# ir2104_V2_0.net
KiCad netlist of a schematic drawn in EasyEDA Pro
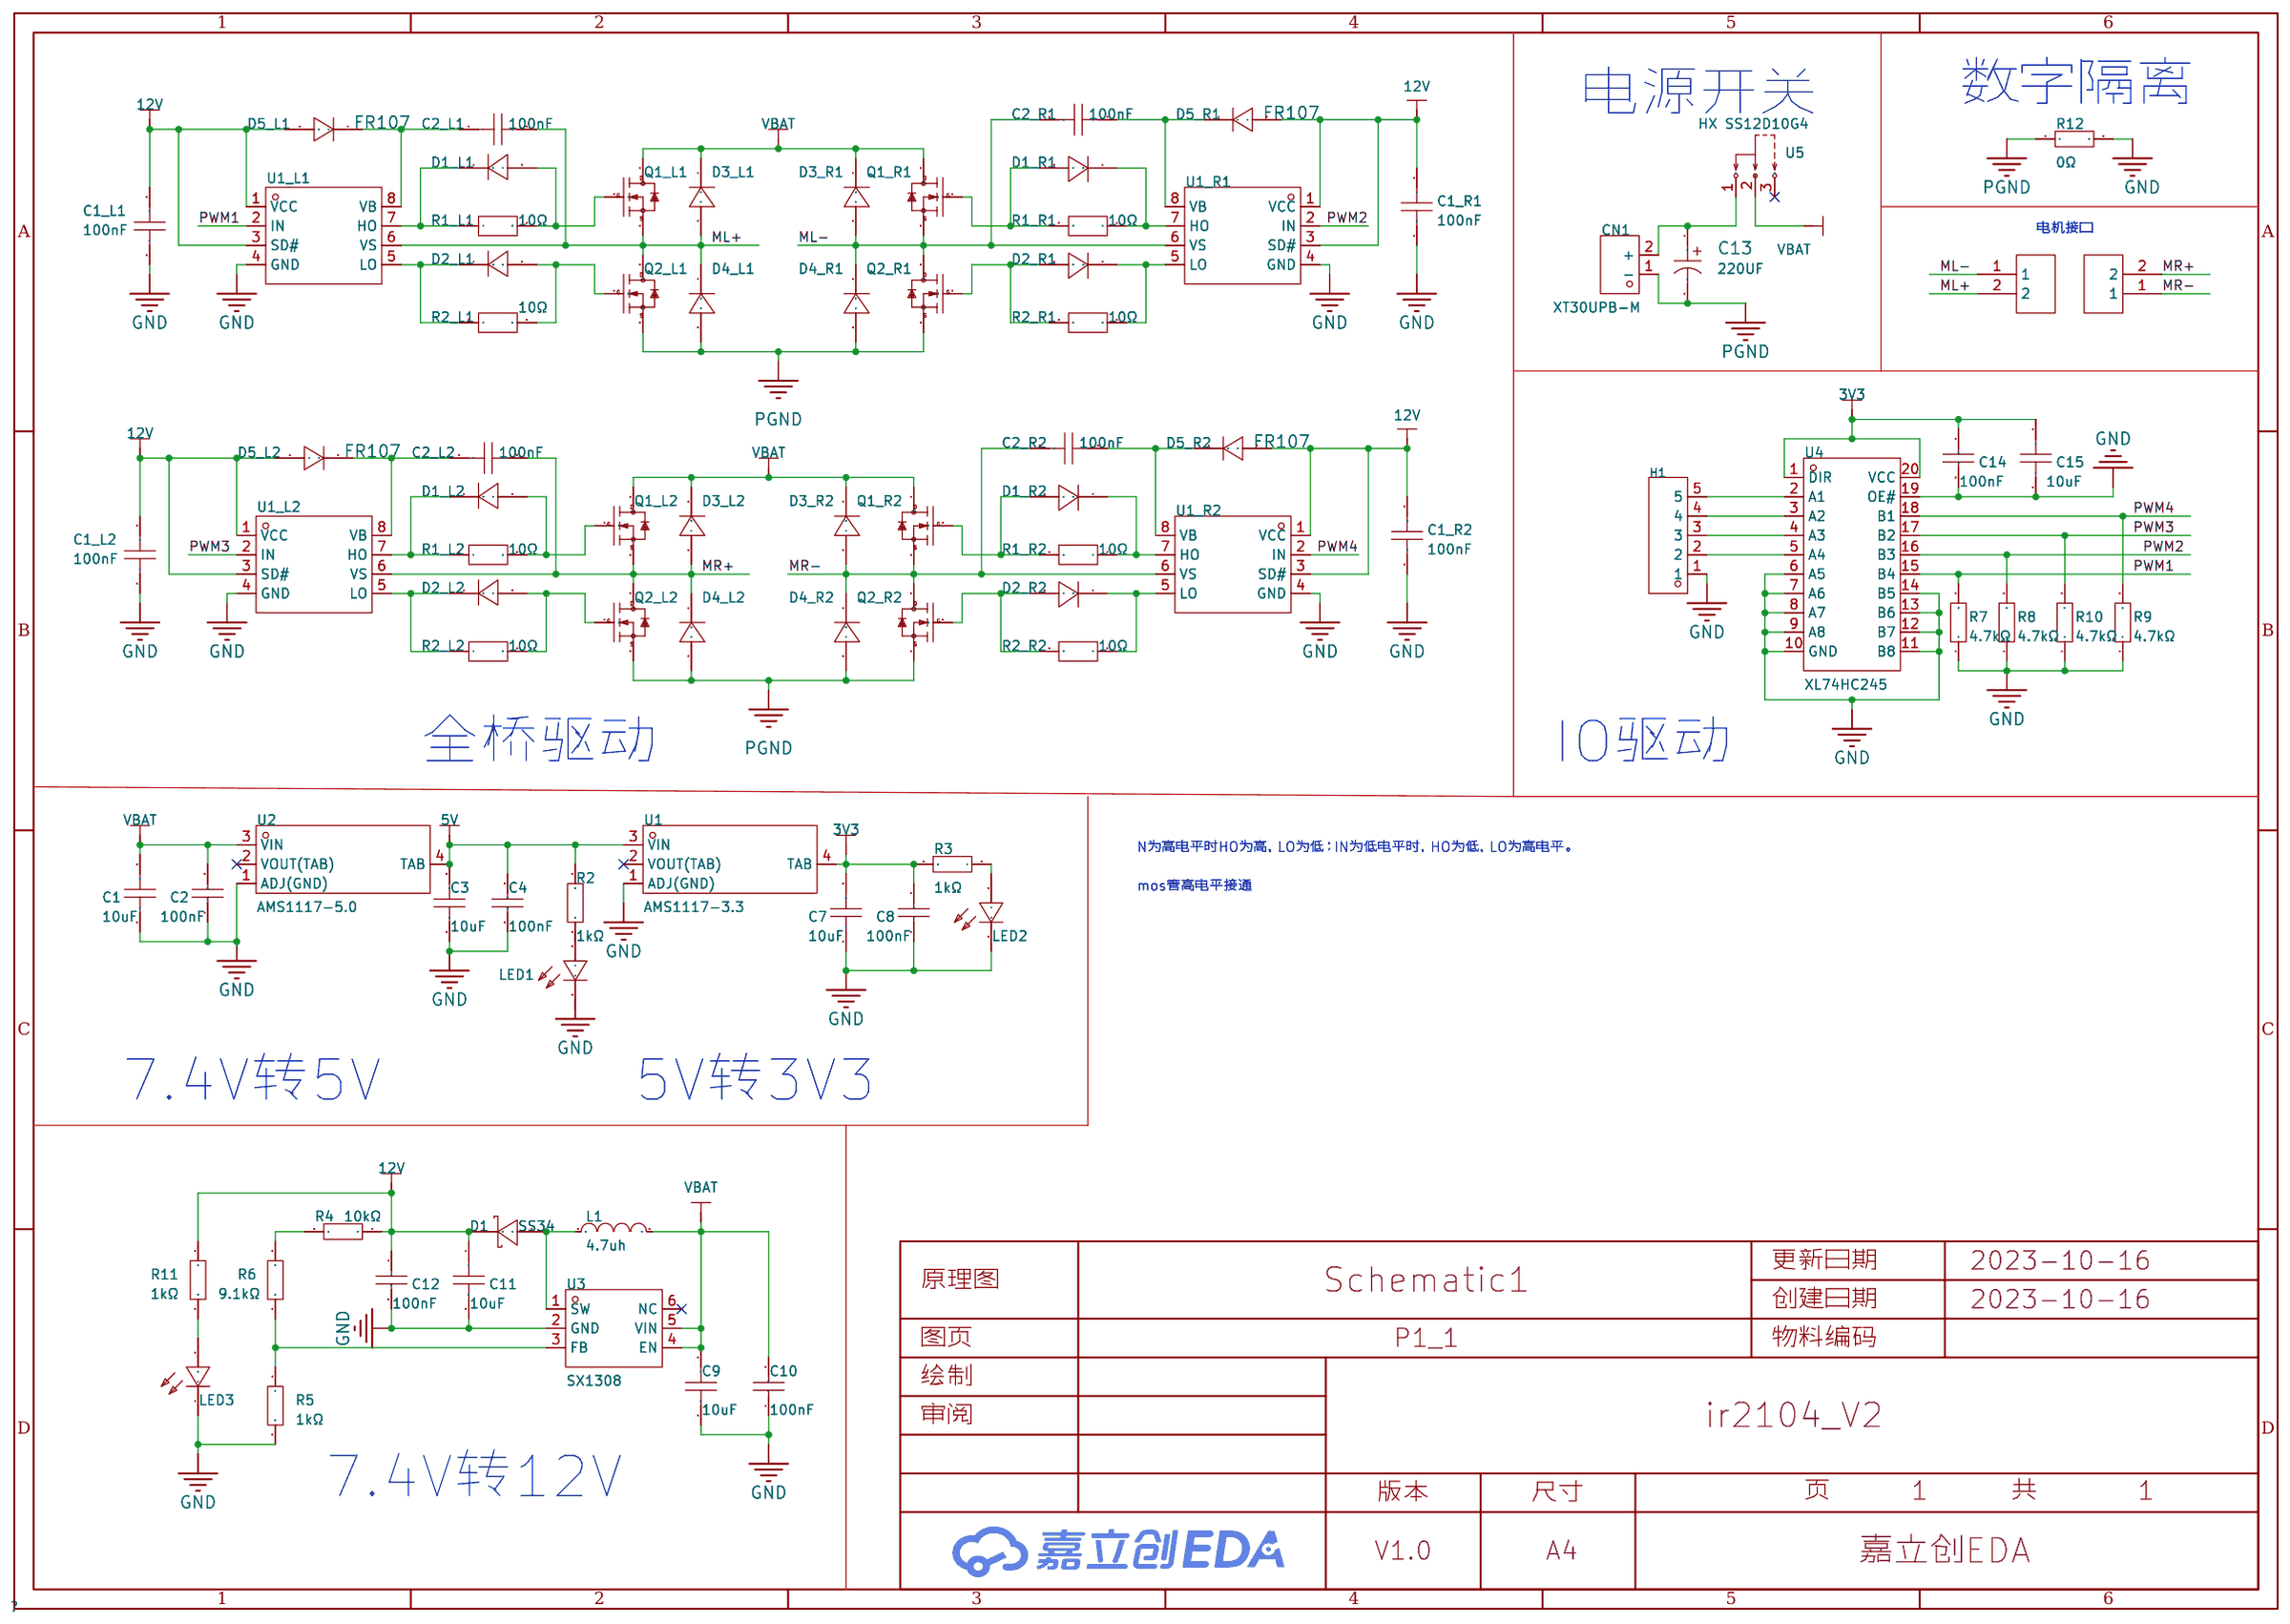
[diagram p0: schematic sheet]

(export (version "E")
  (design (tool "Eeschema 10.0.6"))
  (components
    (comp (ref "C1")
      (value "10uF")
      (footprint "easyedapro:C0603")
      (description "容值:10uF;精度:±20%;额定电压:25V;材质(温度系数):X5R;")
      (fields
        (field (name "Manufacturer Part") "CL10A106MA8NRNC")
        (field (name "Manufacturer") "SAMSUNG(三星)")
      )
      (libsource (lib "easyedapro") (part "CL10A106MA8NRNC"))
    )
    (comp (ref "C1_L1")
      (value "100nF")
      (footprint "easyedapro:C0603")
      (description "容值:100nF;精度:±10%;额定电压:50V;材质(温度系数):X7R;")
      (fields
        (field (name "Manufacturer Part") "CL10B104KB8NNNC")
        (field (name "Manufacturer") "SAMSUNG(三星)")
      )
      (libsource (lib "easyedapro") (part "CL10B104KB8NNNC"))
    )
    (comp (ref "C1_L2")
      (value "100nF")
      (footprint "easyedapro:C0603")
      (description "容值:100nF;精度:±10%;额定电压:50V;材质(温度系数):X7R;")
      (fields
        (field (name "Manufacturer Part") "CL10B104KB8NNNC")
        (field (name "Manufacturer") "SAMSUNG(三星)")
      )
      (libsource (lib "easyedapro") (part "CL10B104KB8NNNC"))
    )
    (comp (ref "C1_R1")
      (value "100nF")
      (footprint "easyedapro:C0603")
      (description "容值:100nF;精度:±10%;额定电压:50V;材质(温度系数):X7R;")
      (fields
        (field (name "Manufacturer Part") "CL10B104KB8NNNC")
        (field (name "Manufacturer") "SAMSUNG(三星)")
      )
      (libsource (lib "easyedapro") (part "CL10B104KB8NNNC"))
    )
    (comp (ref "C1_R2")
      (value "100nF")
      (footprint "easyedapro:C0603")
      (description "容值:100nF;精度:±10%;额定电压:50V;材质(温度系数):X7R;")
      (fields
        (field (name "Manufacturer Part") "CL10B104KB8NNNC")
        (field (name "Manufacturer") "SAMSUNG(三星)")
      )
      (libsource (lib "easyedapro") (part "CL10B104KB8NNNC"))
    )
    (comp (ref "C2")
      (value "100nF")
      (footprint "easyedapro:C0603")
      (description "容值:100nF;精度:±10%;额定电压:50V;材质(温度系数):X7R;")
      (fields (field (name "Manufacturer Part") "0603B104K500NT") (field (name "Manufacturer") "FH(风华)"))
      (libsource (lib "easyedapro") (part "0603B104K500NT"))
    )
    (comp (ref "C2_L1")
      (value "100nF")
      (footprint "easyedapro:C0603")
      (description "容值:100nF;精度:±10%;额定电压:50V;材质(温度系数):X7R;")
      (fields
        (field (name "Manufacturer Part") "CL10B104KB8NNNC")
        (field (name "Manufacturer") "SAMSUNG(三星)")
      )
      (libsource (lib "easyedapro") (part "CL10B104KB8NNNC"))
    )
    (comp (ref "C2_L2")
      (value "100nF")
      (footprint "easyedapro:C0603")
      (description "容值:100nF;精度:±10%;额定电压:50V;材质(温度系数):X7R;")
      (fields
        (field (name "Manufacturer Part") "CL10B104KB8NNNC")
        (field (name "Manufacturer") "SAMSUNG(三星)")
      )
      (libsource (lib "easyedapro") (part "CL10B104KB8NNNC"))
    )
    (comp (ref "C2_R1")
      (value "100nF")
      (footprint "easyedapro:C0603")
      (description "容值:100nF;精度:±10%;额定电压:50V;材质(温度系数):X7R;")
      (fields
        (field (name "Manufacturer Part") "CL10B104KB8NNNC")
        (field (name "Manufacturer") "SAMSUNG(三星)")
      )
      (libsource (lib "easyedapro") (part "CL10B104KB8NNNC"))
    )
    (comp (ref "C2_R2")
      (value "100nF")
      (footprint "easyedapro:C0603")
      (description "容值:100nF;精度:±10%;额定电压:50V;材质(温度系数):X7R;")
      (fields
        (field (name "Manufacturer Part") "CL10B104KB8NNNC")
        (field (name "Manufacturer") "SAMSUNG(三星)")
      )
      (libsource (lib "easyedapro") (part "CL10B104KB8NNNC"))
    )
    (comp (ref "C3")
      (value "10uF")
      (footprint "easyedapro:C0603")
      (description "容值:10uF;精度:±20%;额定电压:25V;材质(温度系数):X5R;")
      (fields
        (field (name "Manufacturer Part") "CL10A106MA8NRNC")
        (field (name "Manufacturer") "SAMSUNG(三星)")
      )
      (libsource (lib "easyedapro") (part "CL10A106MA8NRNC"))
    )
    (comp (ref "C4")
      (value "100nF")
      (footprint "easyedapro:C0603")
      (description "容值:100nF;精度:±10%;额定电压:50V;材质(温度系数):X7R;")
      (fields (field (name "Manufacturer Part") "0603B104K500NT") (field (name "Manufacturer") "FH(风华)"))
      (libsource (lib "easyedapro") (part "0603B104K500NT"))
    )
    (comp (ref "C7")
      (value "10uF")
      (footprint "easyedapro:C0603")
      (description "容值:10uF;精度:±20%;额定电压:25V;材质(温度系数):X5R;")
      (fields
        (field (name "Manufacturer Part") "CL10A106MA8NRNC")
        (field (name "Manufacturer") "SAMSUNG(三星)")
      )
      (libsource (lib "easyedapro") (part "CL10A106MA8NRNC"))
    )
    (comp (ref "C8")
      (value "100nF")
      (footprint "easyedapro:C0603")
      (description "容值:100nF;精度:±10%;额定电压:50V;材质(温度系数):X7R;")
      (fields (field (name "Manufacturer Part") "0603B104K500NT") (field (name "Manufacturer") "FH(风华)"))
      (libsource (lib "easyedapro") (part "0603B104K500NT"))
    )
    (comp (ref "C9")
      (value "10uF")
      (footprint "easyedapro:C0603")
      (description "容值:10uF;精度:±20%;额定电压:25V;材质(温度系数):X5R;")
      (fields
        (field (name "Manufacturer Part") "CL10A106MA8NRNC")
        (field (name "Manufacturer") "SAMSUNG(三星)")
      )
      (libsource (lib "easyedapro") (part "CL10A106MA8NRNC"))
    )
    (comp (ref "C10")
      (value "100nF")
      (footprint "easyedapro:C0603")
      (description "容值:100nF;精度:±10%;额定电压:50V;材质(温度系数):X7R;")
      (fields (field (name "Manufacturer Part") "0603B104K500NT") (field (name "Manufacturer") "FH(风华)"))
      (libsource (lib "easyedapro") (part "0603B104K500NT"))
    )
    (comp (ref "C11")
      (value "10uF")
      (footprint "easyedapro:C0603")
      (description "容值:10uF;精度:±20%;额定电压:25V;材质(温度系数):X5R;")
      (fields
        (field (name "Manufacturer Part") "CL10A106MA8NRNC")
        (field (name "Manufacturer") "SAMSUNG(三星)")
      )
      (libsource (lib "easyedapro") (part "CL10A106MA8NRNC"))
    )
    (comp (ref "C12")
      (value "100nF")
      (footprint "easyedapro:C0603")
      (description "容值:100nF;精度:±10%;额定电压:50V;材质(温度系数):X7R;")
      (fields (field (name "Manufacturer Part") "0603B104K500NT") (field (name "Manufacturer") "FH(风华)"))
      (libsource (lib "easyedapro") (part "0603B104K500NT"))
    )
    (comp (ref "C13")
      (value "220UF")
      (footprint "easyedapro:CAP-SMD_BD8.0-L8.3-W8.3-LS9.3-FD")
      (fields (field (name "Manufacturer") "KNSCHA(科尼盛)"))
      (libsource (lib "easyedapro") (part "FZ470UF16V90RV0148"))
    )
    (comp (ref "C14")
      (value "100nF")
      (footprint "easyedapro:C0603")
      (description "容值:100nF;精度:±10%;额定电压:50V;材质(温度系数):X7R;")
      (fields (field (name "Manufacturer Part") "0603B104K500NT") (field (name "Manufacturer") "FH(风华)"))
      (libsource (lib "easyedapro") (part "0603B104K500NT"))
    )
    (comp (ref "C15")
      (value "10uF")
      (footprint "easyedapro:C0603")
      (description "容值:10uF;精度:±20%;额定电压:25V;材质(温度系数):X5R;")
      (fields
        (field (name "Manufacturer Part") "CL10A106MA8NRNC")
        (field (name "Manufacturer") "SAMSUNG(三星)")
      )
      (libsource (lib "easyedapro") (part "CL10A106MA8NRNC"))
    )
    (comp (ref "CN1")
      (value "XT30UPB-M")
      (footprint "easyedapro:CONN-TH_XT30UPB-M")
      (fields (field (name "Manufacturer") "AMASS(艾迈斯)"))
      (libsource (lib "easyedapro") (part "XT30UPB-M"))
    )
    (comp (ref "D1")
      (value "SS34")
      (footprint "easyedapro:SMA_L4.3-W2.6-LS5.2-RD")
      (description "二极管配置:独立式;直流反向耐压(Vr):40V;平均整流电流(Io):3A;正向压降(Vf):550mV@3A;")
      (fields (field (name "Manufacturer") "MDD"))
      (libsource (lib "easyedapro") (part "SS34_C8678"))
    )
    (comp (ref "D1_L1")
      (value "US1M")
      (footprint "easyedapro:SMA_L4.4-W2.8-LS5.4-RD")
      (fields (field (name "Manufacturer") "MDD"))
      (libsource (lib "easyedapro") (part "US1MG_C412437"))
    )
    (comp (ref "D1_L2")
      (value "US1M")
      (footprint "easyedapro:SMA_L4.4-W2.8-LS5.4-RD")
      (fields (field (name "Manufacturer") "MDD"))
      (libsource (lib "easyedapro") (part "US1MG_C412437"))
    )
    (comp (ref "D1_R1")
      (value "US1M")
      (footprint "easyedapro:SMA_L4.4-W2.8-LS5.4-RD")
      (fields (field (name "Manufacturer") "MDD"))
      (libsource (lib "easyedapro") (part "US1MG_C412437"))
    )
    (comp (ref "D1_R2")
      (value "US1M")
      (footprint "easyedapro:SMA_L4.4-W2.8-LS5.4-RD")
      (fields (field (name "Manufacturer") "MDD"))
      (libsource (lib "easyedapro") (part "US1MG_C412437"))
    )
    (comp (ref "D2_L1")
      (value "US1M")
      (footprint "easyedapro:SMA_L4.4-W2.8-LS5.4-RD")
      (fields (field (name "Manufacturer") "MDD"))
      (libsource (lib "easyedapro") (part "US1MG_C412437"))
    )
    (comp (ref "D2_L2")
      (value "US1M")
      (footprint "easyedapro:SMA_L4.4-W2.8-LS5.4-RD")
      (fields (field (name "Manufacturer") "MDD"))
      (libsource (lib "easyedapro") (part "US1MG_C412437"))
    )
    (comp (ref "D2_R1")
      (value "US1M")
      (footprint "easyedapro:SMA_L4.4-W2.8-LS5.4-RD")
      (fields (field (name "Manufacturer") "MDD"))
      (libsource (lib "easyedapro") (part "US1MG_C412437"))
    )
    (comp (ref "D2_R2")
      (value "US1M")
      (footprint "easyedapro:SMA_L4.4-W2.8-LS5.4-RD")
      (fields (field (name "Manufacturer") "MDD"))
      (libsource (lib "easyedapro") (part "US1MG_C412437"))
    )
    (comp (ref "D3_L1")
      (value "US1M")
      (footprint "easyedapro:SMA_L4.4-W2.8-LS5.4-RD")
      (fields (field (name "Manufacturer") "MDD"))
      (libsource (lib "easyedapro") (part "US1MG_C412437"))
    )
    (comp (ref "D3_L2")
      (value "US1M")
      (footprint "easyedapro:SMA_L4.4-W2.8-LS5.4-RD")
      (fields (field (name "Manufacturer") "MDD"))
      (libsource (lib "easyedapro") (part "US1MG_C412437"))
    )
    (comp (ref "D3_R1")
      (value "US1M")
      (footprint "easyedapro:SMA_L4.4-W2.8-LS5.4-RD")
      (fields (field (name "Manufacturer") "MDD"))
      (libsource (lib "easyedapro") (part "US1MG_C412437"))
    )
    (comp (ref "D3_R2")
      (value "US1M")
      (footprint "easyedapro:SMA_L4.4-W2.8-LS5.4-RD")
      (fields (field (name "Manufacturer") "MDD"))
      (libsource (lib "easyedapro") (part "US1MG_C412437"))
    )
    (comp (ref "D4_L1")
      (value "US1M")
      (footprint "easyedapro:SMA_L4.4-W2.8-LS5.4-RD")
      (fields (field (name "Manufacturer") "MDD"))
      (libsource (lib "easyedapro") (part "US1MG_C412437"))
    )
    (comp (ref "D4_L2")
      (value "US1M")
      (footprint "easyedapro:SMA_L4.4-W2.8-LS5.4-RD")
      (fields (field (name "Manufacturer") "MDD"))
      (libsource (lib "easyedapro") (part "US1MG_C412437"))
    )
    (comp (ref "D4_R1")
      (value "US1M")
      (footprint "easyedapro:SMA_L4.4-W2.8-LS5.4-RD")
      (fields (field (name "Manufacturer") "MDD"))
      (libsource (lib "easyedapro") (part "US1MG_C412437"))
    )
    (comp (ref "D4_R2")
      (value "US1M")
      (footprint "easyedapro:SMA_L4.4-W2.8-LS5.4-RD")
      (fields (field (name "Manufacturer") "MDD"))
      (libsource (lib "easyedapro") (part "US1MG_C412437"))
    )
    (comp (ref "D5_L1")
      (value "FR107")
      (footprint "easyedapro:SOD-123_L2.8-W1.8-LS3.7-RD")
      (fields (field (name "Manufacturer") "BORN(伯恩半导体)"))
      (libsource (lib "easyedapro") (part "FR107_C511885"))
    )
    (comp (ref "D5_L2")
      (value "FR107")
      (footprint "easyedapro:SOD-123_L2.8-W1.8-LS3.7-RD")
      (fields (field (name "Manufacturer") "BORN(伯恩半导体)"))
      (libsource (lib "easyedapro") (part "FR107_C511885"))
    )
    (comp (ref "D5_R1")
      (value "FR107")
      (footprint "easyedapro:SOD-123_L2.8-W1.8-LS3.7-RD")
      (fields (field (name "Manufacturer") "BORN(伯恩半导体)"))
      (libsource (lib "easyedapro") (part "FR107_C511885"))
    )
    (comp (ref "D5_R2")
      (value "FR107")
      (footprint "easyedapro:SOD-123_L2.8-W1.8-LS3.7-RD")
      (fields (field (name "Manufacturer") "BORN(伯恩半导体)"))
      (libsource (lib "easyedapro") (part "FR107_C511885"))
    )
    (comp (ref "H1")
      (value "PZ254V-11-05P")
      (footprint "easyedapro:HDR-TH_5P-P2.54-V-M")
      (fields (field (name "Manufacturer") "XFCN(兴飞)"))
      (libsource (lib "easyedapro") (part "PZ254V-11-05P"))
    )
    (comp (ref "L1")
      (value "4.7uh")
      (footprint "easyedapro:IND-SMD_L7.3-W6.6")
      (description "电感值:10uH;精度:±20%;额定电流:-;")
      (fields (field (name "Manufacturer Part") "SMMS0630-100M") (field (name "Manufacturer") "SXN(顺翔诺)"))
      (libsource (lib "easyedapro") (part "SMMS0630-100M"))
    )
    (comp (ref "LED1")
      (value "NCD0603R1")
      (footprint "easyedapro:LED0603-RD_RED")
      (description "发光颜色:红灯;")
      (fields (field (name "Manufacturer") "国星光电"))
      (libsource (lib "easyedapro") (part "FC-DA1608HRK-620D"))
    )
    (comp (ref "LED2")
      (value "NCD0603R1")
      (footprint "easyedapro:LED0603-RD_RED")
      (description "发光颜色:红灯;")
      (fields (field (name "Manufacturer") "国星光电"))
      (libsource (lib "easyedapro") (part "FC-DA1608HRK-620D"))
    )
    (comp (ref "LED3")
      (value "NCD0603R1")
      (footprint "easyedapro:LED0603-RD_RED")
      (description "发光颜色:红灯;")
      (fields (field (name "Manufacturer") "国星光电"))
      (libsource (lib "easyedapro") (part "FC-DA1608HRK-620D"))
    )
    (comp (ref "P1")
      (value "WJ500V-5.08-2P")
      (footprint "easyedapro:CONN-TH_2P-P5.00_WJ500V-5.08-2P")
      (fields (field (name "Manufacturer") "KANGNEX(康奈克斯电气)"))
      (libsource (lib "easyedapro") (part "WJ500V-5.08-2P-14-00A"))
    )
    (comp (ref "P2")
      (value "WJ500V-5.08-2P")
      (footprint "easyedapro:CONN-TH_2P-P5.00_WJ500V-5.08-2P")
      (fields (field (name "Manufacturer") "KANGNEX(康奈克斯电气)"))
      (libsource (lib "easyedapro") (part "WJ500V-5.08-2P-14-00A"))
    )
    (comp (ref "Q1_L1")
      (value "IRFR3607TRPBF")
      (footprint "easyedapro:TO-252-3_L6.5-W5.8-P4.58-BL")
      (fields (field (name "Manufacturer") "Infineon(英飞凌)"))
      (libsource (lib "easyedapro") (part "IRFR3607TRPBF"))
    )
    (comp (ref "Q1_L2")
      (value "IRFR3607TRPBF")
      (footprint "easyedapro:TO-252-3_L6.5-W5.8-P4.58-BL")
      (fields (field (name "Manufacturer") "Infineon(英飞凌)"))
      (libsource (lib "easyedapro") (part "IRFR3607TRPBF"))
    )
    (comp (ref "Q1_R1")
      (value "IRFR3607TRPBF")
      (footprint "easyedapro:TO-252-3_L6.5-W5.8-P4.58-BL")
      (fields (field (name "Manufacturer") "Infineon(英飞凌)"))
      (libsource (lib "easyedapro") (part "IRFR3607TRPBF"))
    )
    (comp (ref "Q1_R2")
      (value "IRFR3607TRPBF")
      (footprint "easyedapro:TO-252-3_L6.5-W5.8-P4.58-BL")
      (fields (field (name "Manufacturer") "Infineon(英飞凌)"))
      (libsource (lib "easyedapro") (part "IRFR3607TRPBF"))
    )
    (comp (ref "Q2_L1")
      (value "IRFR3607TRPBF")
      (footprint "easyedapro:TO-252-3_L6.5-W5.8-P4.58-BL")
      (fields (field (name "Manufacturer") "Infineon(英飞凌)"))
      (libsource (lib "easyedapro") (part "IRFR3607TRPBF"))
    )
    (comp (ref "Q2_L2")
      (value "IRFR3607TRPBF")
      (footprint "easyedapro:TO-252-3_L6.5-W5.8-P4.58-BL")
      (fields (field (name "Manufacturer") "Infineon(英飞凌)"))
      (libsource (lib "easyedapro") (part "IRFR3607TRPBF"))
    )
    (comp (ref "Q2_R1")
      (value "IRFR3607TRPBF")
      (footprint "easyedapro:TO-252-3_L6.5-W5.8-P4.58-BL")
      (fields (field (name "Manufacturer") "Infineon(英飞凌)"))
      (libsource (lib "easyedapro") (part "IRFR3607TRPBF"))
    )
    (comp (ref "Q2_R2")
      (value "IRFR3607TRPBF")
      (footprint "easyedapro:TO-252-3_L6.5-W5.8-P4.58-BL")
      (fields (field (name "Manufacturer") "Infineon(英飞凌)"))
      (libsource (lib "easyedapro") (part "IRFR3607TRPBF"))
    )
    (comp (ref "R1_L1")
      (value "10Ω")
      (footprint "easyedapro:R0603")
      (description "阻值:10Ω;精度:±0.5%;功率:250mW;")
      (fields (field (name "Manufacturer Part") "ERJUP3D10R0V") (field (name "Manufacturer") "PANASONIC(松下)"))
      (libsource (lib "easyedapro") (part "ERJUP3D10R0V"))
    )
    (comp (ref "R1_L2")
      (value "10Ω")
      (footprint "easyedapro:R0603")
      (description "阻值:10Ω;精度:±0.5%;功率:250mW;")
      (fields (field (name "Manufacturer Part") "ERJUP3D10R0V") (field (name "Manufacturer") "PANASONIC(松下)"))
      (libsource (lib "easyedapro") (part "ERJUP3D10R0V"))
    )
    (comp (ref "R1_R1")
      (value "10Ω")
      (footprint "easyedapro:R0603")
      (description "阻值:10Ω;精度:±0.5%;功率:250mW;")
      (fields (field (name "Manufacturer Part") "ERJUP3D10R0V") (field (name "Manufacturer") "PANASONIC(松下)"))
      (libsource (lib "easyedapro") (part "ERJUP3D10R0V"))
    )
    (comp (ref "R1_R2")
      (value "10Ω")
      (footprint "easyedapro:R0603")
      (description "阻值:10Ω;精度:±0.5%;功率:250mW;")
      (fields (field (name "Manufacturer Part") "ERJUP3D10R0V") (field (name "Manufacturer") "PANASONIC(松下)"))
      (libsource (lib "easyedapro") (part "ERJUP3D10R0V"))
    )
    (comp (ref "R2")
      (value "1kΩ")
      (footprint "easyedapro:R0603")
      (description "电阻类型:厚膜电阻;阻值:1kΩ;精度:±1%;功率:100mW;")
      (fields
        (field (name "Manufacturer Part") "0603WAF1001T5E")
        (field (name "Manufacturer") "UNI-ROYAL(厚声)")
      )
      (libsource (lib "easyedapro") (part "0603WAF1001T5E"))
    )
    (comp (ref "R2_L1")
      (value "10Ω")
      (footprint "easyedapro:R0603")
      (description "阻值:10Ω;精度:±0.5%;功率:250mW;")
      (fields (field (name "Manufacturer Part") "ERJUP3D10R0V") (field (name "Manufacturer") "PANASONIC(松下)"))
      (libsource (lib "easyedapro") (part "ERJUP3D10R0V"))
    )
    (comp (ref "R2_L2")
      (value "10Ω")
      (footprint "easyedapro:R0603")
      (description "阻值:10Ω;精度:±0.5%;功率:250mW;")
      (fields (field (name "Manufacturer Part") "ERJUP3D10R0V") (field (name "Manufacturer") "PANASONIC(松下)"))
      (libsource (lib "easyedapro") (part "ERJUP3D10R0V"))
    )
    (comp (ref "R2_R1")
      (value "10Ω")
      (footprint "easyedapro:R0603")
      (description "阻值:10Ω;精度:±0.5%;功率:250mW;")
      (fields (field (name "Manufacturer Part") "ERJUP3D10R0V") (field (name "Manufacturer") "PANASONIC(松下)"))
      (libsource (lib "easyedapro") (part "ERJUP3D10R0V"))
    )
    (comp (ref "R2_R2")
      (value "10Ω")
      (footprint "easyedapro:R0603")
      (description "阻值:10Ω;精度:±0.5%;功率:250mW;")
      (fields (field (name "Manufacturer Part") "ERJUP3D10R0V") (field (name "Manufacturer") "PANASONIC(松下)"))
      (libsource (lib "easyedapro") (part "ERJUP3D10R0V"))
    )
    (comp (ref "R3")
      (value "1kΩ")
      (footprint "easyedapro:R0603")
      (description "电阻类型:厚膜电阻;阻值:1kΩ;精度:±1%;功率:100mW;")
      (fields
        (field (name "Manufacturer Part") "0603WAF1001T5E")
        (field (name "Manufacturer") "UNI-ROYAL(厚声)")
      )
      (libsource (lib "easyedapro") (part "0603WAF1001T5E"))
    )
    (comp (ref "R4")
      (value "10kΩ")
      (footprint "easyedapro:R0603")
      (description "电阻类型:薄膜电阻;阻值:10kΩ;精度:±0.1%;功率:100mW;")
      (fields (field (name "Manufacturer Part") "RT0603BRD0710KL") (field (name "Manufacturer") "YAGEO(国巨)"))
      (libsource (lib "easyedapro") (part "RT0603BRD0710KL"))
    )
    (comp (ref "R5")
      (value "1kΩ")
      (footprint "easyedapro:R0603")
      (description "电阻类型:薄膜电阻;阻值:1kΩ;精度:±0.1%;功率:100mW;")
      (fields (field (name "Manufacturer Part") "RT0603BRD071KL") (field (name "Manufacturer") "YAGEO(国巨)"))
      (libsource (lib "easyedapro") (part "RT0603BRD071KL"))
    )
    (comp (ref "R6")
      (value "9.1kΩ")
      (footprint "easyedapro:R0603")
      (description "电阻类型:薄膜电阻;阻值:9.1kΩ;精度:±0.1%;功率:100mW;")
      (fields (field (name "Manufacturer Part") "PTFR0603B9K10P9") (field (name "Manufacturer") "RESI(开步睿思）"))
      (libsource (lib "easyedapro") (part "PTFR0603B9K10P9"))
    )
    (comp (ref "R7")
      (value "4.7kΩ")
      (footprint "easyedapro:R0603")
      (description "电阻类型:厚膜电阻;阻值:4.7kΩ;精度:±1%;功率:100mW;")
      (fields
        (field (name "Manufacturer Part") "0603WAF4701T5E")
        (field (name "Manufacturer") "UNI-ROYAL(厚声)")
      )
      (libsource (lib "easyedapro") (part "0603WAF4701T5E"))
    )
    (comp (ref "R8")
      (value "4.7kΩ")
      (footprint "easyedapro:R0603")
      (description "电阻类型:厚膜电阻;阻值:4.7kΩ;精度:±1%;功率:100mW;")
      (fields
        (field (name "Manufacturer Part") "0603WAF4701T5E")
        (field (name "Manufacturer") "UNI-ROYAL(厚声)")
      )
      (libsource (lib "easyedapro") (part "0603WAF4701T5E"))
    )
    (comp (ref "R9")
      (value "4.7kΩ")
      (footprint "easyedapro:R0603")
      (description "电阻类型:厚膜电阻;阻值:4.7kΩ;精度:±1%;功率:100mW;")
      (fields
        (field (name "Manufacturer Part") "0603WAF4701T5E")
        (field (name "Manufacturer") "UNI-ROYAL(厚声)")
      )
      (libsource (lib "easyedapro") (part "0603WAF4701T5E"))
    )
    (comp (ref "R10")
      (value "4.7kΩ")
      (footprint "easyedapro:R0603")
      (description "电阻类型:厚膜电阻;阻值:4.7kΩ;精度:±1%;功率:100mW;")
      (fields
        (field (name "Manufacturer Part") "0603WAF4701T5E")
        (field (name "Manufacturer") "UNI-ROYAL(厚声)")
      )
      (libsource (lib "easyedapro") (part "0603WAF4701T5E"))
    )
    (comp (ref "R11")
      (value "1kΩ")
      (footprint "easyedapro:R0603")
      (description "电阻类型:厚膜电阻;阻值:1kΩ;精度:±1%;功率:100mW;")
      (fields
        (field (name "Manufacturer Part") "0603WAF1001T5E")
        (field (name "Manufacturer") "UNI-ROYAL(厚声)")
      )
      (libsource (lib "easyedapro") (part "0603WAF1001T5E"))
    )
    (comp (ref "R12")
      (value "0Ω")
      (footprint "easyedapro:R0805")
      (description "电阻类型:厚膜电阻;阻值:0Ω;精度:±1%;功率:125mW;")
      (fields
        (field (name "Manufacturer Part") "0805W8F0000T5E")
        (field (name "Manufacturer") "UNI-ROYAL(厚声)")
      )
      (libsource (lib "easyedapro") (part "0805W8F0000T5E"))
    )
    (comp (ref "U1")
      (value "AMS1117-3.3")
      (footprint "easyedapro:SOT-223-4_L6.5-W3.5-P2.30-LS7.0-BR")
      (description "输出类型:固定;输出极性:正;最大输入电压:18V;输出电压:3.3V;输出电流:1A;电源纹波抑制比(PSRR):60dB@(120Hz);")
      (fields (field (name "Manufacturer") "UMW(广东友台半导体)"))
      (libsource (lib "easyedapro") (part "AMS1117-3.3_C347222"))
    )
    (comp (ref "U1_L1")
      (value "EG2104")
      (footprint "easyedapro:SOP-8_L5.0-W4.0-P1.27-LS6.2-BL")
      (description "高性价比, 600V，半桥式Nmos预驱动器")
      (fields (field (name "Manufacturer") "EG(屹晶微)"))
      (libsource (lib "easyedapro") (part "EG2104"))
    )
    (comp (ref "U1_L2")
      (value "EG2104")
      (footprint "easyedapro:SOP-8_L5.0-W4.0-P1.27-LS6.2-BL")
      (description "高性价比, 600V，半桥式Nmos预驱动器")
      (fields (field (name "Manufacturer") "EG(屹晶微)"))
      (libsource (lib "easyedapro") (part "EG2104"))
    )
    (comp (ref "U1_R1")
      (value "EG2104")
      (footprint "easyedapro:SOP-8_L5.0-W4.0-P1.27-LS6.2-BL")
      (description "高性价比, 600V，半桥式Nmos预驱动器")
      (fields (field (name "Manufacturer") "EG(屹晶微)"))
      (libsource (lib "easyedapro") (part "EG2104"))
    )
    (comp (ref "U1_R2")
      (value "EG2104")
      (footprint "easyedapro:SOP-8_L5.0-W4.0-P1.27-LS6.2-BL")
      (description "高性价比, 600V，半桥式Nmos预驱动器")
      (fields (field (name "Manufacturer") "EG(屹晶微)"))
      (libsource (lib "easyedapro") (part "EG2104"))
    )
    (comp (ref "U2")
      (value "AMS1117-5.0")
      (footprint "easyedapro:SOT-223_L6.7-W3.5-P2.30-BR")
      (description "输出类型:固定;输出极性:正;最大输入电压:18V;输出电压:5V;输出电流:1A;电源纹波抑制比(PSRR):60dB@(120Hz);")
      (fields (field (name "Manufacturer") "UMW(广东友台半导体)"))
      (libsource (lib "easyedapro") (part "AMS1117-5.0_C347223"))
    )
    (comp (ref "U3")
      (value "SX1308")
      (footprint "easyedapro:SOT-23-6_L2.9-W1.6-P0.95-LS2.8-BL")
      (description "功能类型:升压型;同步整流:否;输出通道数:1;拓扑结构:升压式;输入电压:2V~24V;输出电压:28V;输出电流(最大值):-;开关频率:1.2MHz;")
      (fields (field (name "Manufacturer") "SX(硕芯科技)"))
      (libsource (lib "easyedapro") (part "SX1308"))
    )
    (comp (ref "U4")
      (value "XL74HC245")
      (footprint "easyedapro:SOP-20_L12.8-W7.5-P1.27-LS10.4-BL")
      (description "八路总线收发器")
      (fields (field (name "Manufacturer") "XINLUDA(信路达)"))
      (libsource (lib "easyedapro") (part "XL74HC245"))
    )
    (comp (ref "U5")
      (value "HX SS12D10G4")
      (footprint "easyedapro:SW-TH_SHOU-HAN_SS12D10G4")
      (fields (field (name "Manufacturer") "hanxia(韩下)"))
      (libsource (lib "easyedapro") (part "HX SS12D10G4"))
    )
  )
  (nets
    (net (code "1") (name "/ML+") (class "Default")
      (node (ref "C2_L1") (pin "2") (pinfunction "2_2") (pintype "input"))
      (node (ref "D3_L1") (pin "2") (pinfunction "A_2") (pintype "input"))
      (node (ref "D4_L1") (pin "1") (pinfunction "C_1") (pintype "input"))
      (node (ref "P1") (pin "2") (pinfunction "2_2") (pintype "input"))
      (node (ref "Q1_L1") (pin "3") (pinfunction "S_3") (pintype "input"))
      (node (ref "Q2_L1") (pin "2") (pinfunction "D_2") (pintype "input"))
      (node (ref "U1_L1") (pin "6") (pinfunction "VS_6") (pintype "input"))
    )
    (net (code "2") (name "/ML-") (class "Default")
      (node (ref "C2_R1") (pin "2") (pinfunction "2_2") (pintype "input"))
      (node (ref "D3_R1") (pin "2") (pinfunction "A_2") (pintype "input"))
      (node (ref "D4_R1") (pin "1") (pinfunction "C_1") (pintype "input"))
      (node (ref "P1") (pin "1") (pinfunction "1_1") (pintype "input"))
      (node (ref "Q1_R1") (pin "3") (pinfunction "S_3") (pintype "input"))
      (node (ref "Q2_R1") (pin "2") (pinfunction "D_2") (pintype "input"))
      (node (ref "U1_R1") (pin "6") (pinfunction "VS_6") (pintype "input"))
    )
    (net (code "3") (name "/MR+") (class "Default")
      (node (ref "C2_L2") (pin "2") (pinfunction "2_2") (pintype "input"))
      (node (ref "D3_L2") (pin "2") (pinfunction "A_2") (pintype "input"))
      (node (ref "D4_L2") (pin "1") (pinfunction "C_1") (pintype "input"))
      (node (ref "P2") (pin "2") (pinfunction "2_2") (pintype "input"))
      (node (ref "Q1_L2") (pin "3") (pinfunction "S_3") (pintype "input"))
      (node (ref "Q2_L2") (pin "2") (pinfunction "D_2") (pintype "input"))
      (node (ref "U1_L2") (pin "6") (pinfunction "VS_6") (pintype "input"))
    )
    (net (code "4") (name "/MR-") (class "Default")
      (node (ref "C2_R2") (pin "2") (pinfunction "2_2") (pintype "input"))
      (node (ref "D3_R2") (pin "2") (pinfunction "A_2") (pintype "input"))
      (node (ref "D4_R2") (pin "1") (pinfunction "C_1") (pintype "input"))
      (node (ref "P2") (pin "1") (pinfunction "1_1") (pintype "input"))
      (node (ref "Q1_R2") (pin "3") (pinfunction "S_3") (pintype "input"))
      (node (ref "Q2_R2") (pin "2") (pinfunction "D_2") (pintype "input"))
      (node (ref "U1_R2") (pin "6") (pinfunction "VS_6") (pintype "input"))
    )
    (net (code "5") (name "/PWM1") (class "Default")
      (node (ref "R7") (pin "2") (pinfunction "2_2") (pintype "input"))
      (node (ref "U1_L1") (pin "2") (pinfunction "IN_2") (pintype "input"))
      (node (ref "U4") (pin "15") (pinfunction "B4_15") (pintype "input"))
    )
    (net (code "6") (name "/PWM2") (class "Default")
      (node (ref "R8") (pin "2") (pinfunction "2_2") (pintype "input"))
      (node (ref "U1_R1") (pin "2") (pinfunction "IN_2") (pintype "input"))
      (node (ref "U4") (pin "16") (pinfunction "B3_16") (pintype "input"))
    )
    (net (code "7") (name "/PWM3") (class "Default")
      (node (ref "R10") (pin "2") (pinfunction "2_2") (pintype "input"))
      (node (ref "U1_L2") (pin "2") (pinfunction "IN_2") (pintype "input"))
      (node (ref "U4") (pin "17") (pinfunction "B2_17") (pintype "input"))
    )
    (net (code "8") (name "/PWM4") (class "Default")
      (node (ref "R9") (pin "2") (pinfunction "2_2") (pintype "input"))
      (node (ref "U1_R2") (pin "2") (pinfunction "IN_2") (pintype "input"))
      (node (ref "U4") (pin "18") (pinfunction "B1_18") (pintype "input"))
    )
    (net (code "9") (name "3V3") (class "Default")
      (node (ref "C14") (pin "1") (pinfunction "1_1") (pintype "input"))
      (node (ref "C15") (pin "1") (pinfunction "1_1") (pintype "input"))
      (node (ref "C7") (pin "2") (pinfunction "2_2") (pintype "input"))
      (node (ref "C8") (pin "2") (pinfunction "2_2") (pintype "input"))
      (node (ref "R3") (pin "2") (pinfunction "2_2") (pintype "input"))
      (node (ref "U1") (pin "4") (pinfunction "TAB_4") (pintype "input"))
      (node (ref "U4") (pin "1") (pinfunction "DIR_1") (pintype "input"))
      (node (ref "U4") (pin "20") (pinfunction "VCC_20") (pintype "input"))
    )
    (net (code "10") (name "5V") (class "Default")
      (node (ref "C3") (pin "2") (pinfunction "2_2") (pintype "input"))
      (node (ref "C4") (pin "2") (pinfunction "2_2") (pintype "input"))
      (node (ref "R2") (pin "1") (pinfunction "1_1") (pintype "input"))
      (node (ref "U1") (pin "3") (pinfunction "VIN_3") (pintype "input"))
      (node (ref "U2") (pin "4") (pinfunction "TAB_4") (pintype "input"))
    )
    (net (code "11") (name "12V") (class "Default")
      (node (ref "C11") (pin "1") (pinfunction "1_1") (pintype "input"))
      (node (ref "C12") (pin "1") (pinfunction "1_1") (pintype "input"))
      (node (ref "C1_L1") (pin "2") (pinfunction "2_2") (pintype "input"))
      (node (ref "C1_L2") (pin "2") (pinfunction "2_2") (pintype "input"))
      (node (ref "C1_R1") (pin "2") (pinfunction "2_2") (pintype "input"))
      (node (ref "C1_R2") (pin "2") (pinfunction "2_2") (pintype "input"))
      (node (ref "D1") (pin "1") (pinfunction "K_1") (pintype "input"))
      (node (ref "D5_L1") (pin "2") (pinfunction "A_2") (pintype "input"))
      (node (ref "D5_L2") (pin "2") (pinfunction "A_2") (pintype "input"))
      (node (ref "D5_R1") (pin "2") (pinfunction "A_2") (pintype "input"))
      (node (ref "D5_R2") (pin "2") (pinfunction "A_2") (pintype "input"))
      (node (ref "R11") (pin "1") (pinfunction "1_1") (pintype "input"))
      (node (ref "R4") (pin "1") (pinfunction "1_1") (pintype "input"))
      (node (ref "U1_L1") (pin "1") (pinfunction "VCC_1") (pintype "input"))
      (node (ref "U1_L1") (pin "3") (pinfunction "SD#_3") (pintype "input"))
      (node (ref "U1_L2") (pin "1") (pinfunction "VCC_1") (pintype "input"))
      (node (ref "U1_L2") (pin "3") (pinfunction "SD#_3") (pintype "input"))
      (node (ref "U1_R1") (pin "1") (pinfunction "VCC_1") (pintype "input"))
      (node (ref "U1_R1") (pin "3") (pinfunction "SD#_3") (pintype "input"))
      (node (ref "U1_R2") (pin "1") (pinfunction "VCC_1") (pintype "input"))
      (node (ref "U1_R2") (pin "3") (pinfunction "SD#_3") (pintype "input"))
    )
    (net (code "12") (name "GND") (class "Default")
      (node (ref "C1") (pin "1") (pinfunction "1_1") (pintype "input"))
      (node (ref "C10") (pin "1") (pinfunction "1_1") (pintype "input"))
      (node (ref "C11") (pin "2") (pinfunction "2_2") (pintype "input"))
      (node (ref "C12") (pin "2") (pinfunction "2_2") (pintype "input"))
      (node (ref "C14") (pin "2") (pinfunction "2_2") (pintype "input"))
      (node (ref "C15") (pin "2") (pinfunction "2_2") (pintype "input"))
      (node (ref "C1_L1") (pin "1") (pinfunction "1_1") (pintype "input"))
      (node (ref "C1_L2") (pin "1") (pinfunction "1_1") (pintype "input"))
      (node (ref "C1_R1") (pin "1") (pinfunction "1_1") (pintype "input"))
      (node (ref "C1_R2") (pin "1") (pinfunction "1_1") (pintype "input"))
      (node (ref "C2") (pin "1") (pinfunction "1_1") (pintype "input"))
      (node (ref "C3") (pin "1") (pinfunction "1_1") (pintype "input"))
      (node (ref "C4") (pin "1") (pinfunction "1_1") (pintype "input"))
      (node (ref "C7") (pin "1") (pinfunction "1_1") (pintype "input"))
      (node (ref "C8") (pin "1") (pinfunction "1_1") (pintype "input"))
      (node (ref "C9") (pin "1") (pinfunction "1_1") (pintype "input"))
      (node (ref "H1") (pin "1") (pinfunction "1_1") (pintype "input"))
      (node (ref "LED1") (pin "1") (pinfunction "K_1") (pintype "input"))
      (node (ref "LED2") (pin "1") (pinfunction "K_1") (pintype "input"))
      (node (ref "LED3") (pin "1") (pinfunction "K_1") (pintype "input"))
      (node (ref "R10") (pin "1") (pinfunction "1_1") (pintype "input"))
      (node (ref "R12") (pin "2") (pinfunction "2_2") (pintype "input"))
      (node (ref "R5") (pin "2") (pinfunction "2_2") (pintype "input"))
      (node (ref "R7") (pin "1") (pinfunction "1_1") (pintype "input"))
      (node (ref "R8") (pin "1") (pinfunction "1_1") (pintype "input"))
      (node (ref "R9") (pin "1") (pinfunction "1_1") (pintype "input"))
      (node (ref "U1") (pin "1") (pinfunction "ADJ(GND)_1") (pintype "input"))
      (node (ref "U1_L1") (pin "4") (pinfunction "GND_4") (pintype "input"))
      (node (ref "U1_L2") (pin "4") (pinfunction "GND_4") (pintype "input"))
      (node (ref "U1_R1") (pin "4") (pinfunction "GND_4") (pintype "input"))
      (node (ref "U1_R2") (pin "4") (pinfunction "GND_4") (pintype "input"))
      (node (ref "U2") (pin "1") (pinfunction "ADJ(GND)_1") (pintype "input"))
      (node (ref "U3") (pin "2") (pinfunction "GND_2") (pintype "input"))
      (node (ref "U4") (pin "10") (pinfunction "GND_10") (pintype "input"))
      (node (ref "U4") (pin "11") (pinfunction "B8_11") (pintype "input"))
      (node (ref "U4") (pin "12") (pinfunction "B7_12") (pintype "input"))
      (node (ref "U4") (pin "13") (pinfunction "B6_13") (pintype "input"))
      (node (ref "U4") (pin "14") (pinfunction "B5_14") (pintype "input"))
      (node (ref "U4") (pin "19") (pinfunction "OE#_19") (pintype "input"))
      (node (ref "U4") (pin "6") (pinfunction "A5_6") (pintype "input"))
      (node (ref "U4") (pin "7") (pinfunction "A6_7") (pintype "input"))
      (node (ref "U4") (pin "8") (pinfunction "A7_8") (pintype "input"))
      (node (ref "U4") (pin "9") (pinfunction "A8_9") (pintype "input"))
    )
    (net (code "13") (name "Net-(CN1-+)") (class "Default")
      (node (ref "C13") (pin "1") (pinfunction "1_1") (pintype "input"))
      (node (ref "CN1") (pin "2") (pinfunction "+_2") (pintype "input"))
      (node (ref "U5") (pin "1") (pinfunction "1_1") (pintype "input"))
    )
    (net (code "14") (name "Net-(D1-A)") (class "Default")
      (node (ref "D1") (pin "2") (pinfunction "A_2") (pintype "input"))
      (node (ref "L1") (pin "1") (pinfunction "1_1") (pintype "input"))
      (node (ref "U3") (pin "1") (pinfunction "SW_1") (pintype "input"))
    )
    (net (code "15") (name "Net-(D1_L1-A)") (class "Default")
      (node (ref "D1_L1") (pin "2") (pinfunction "A_2") (pintype "input"))
      (node (ref "Q1_L1") (pin "1") (pinfunction "G_1") (pintype "input"))
      (node (ref "R1_L1") (pin "2") (pinfunction "2_2") (pintype "input"))
    )
    (net (code "16") (name "Net-(D1_L1-C)") (class "Default")
      (node (ref "D1_L1") (pin "1") (pinfunction "C_1") (pintype "input"))
      (node (ref "R1_L1") (pin "1") (pinfunction "1_1") (pintype "input"))
      (node (ref "U1_L1") (pin "7") (pinfunction "HO_7") (pintype "input"))
    )
    (net (code "17") (name "Net-(D1_L2-A)") (class "Default")
      (node (ref "D1_L2") (pin "2") (pinfunction "A_2") (pintype "input"))
      (node (ref "Q1_L2") (pin "1") (pinfunction "G_1") (pintype "input"))
      (node (ref "R1_L2") (pin "2") (pinfunction "2_2") (pintype "input"))
    )
    (net (code "18") (name "Net-(D1_L2-C)") (class "Default")
      (node (ref "D1_L2") (pin "1") (pinfunction "C_1") (pintype "input"))
      (node (ref "R1_L2") (pin "1") (pinfunction "1_1") (pintype "input"))
      (node (ref "U1_L2") (pin "7") (pinfunction "HO_7") (pintype "input"))
    )
    (net (code "19") (name "Net-(D1_R1-A)") (class "Default")
      (node (ref "D1_R1") (pin "2") (pinfunction "A_2") (pintype "input"))
      (node (ref "Q1_R1") (pin "1") (pinfunction "G_1") (pintype "input"))
      (node (ref "R1_R1") (pin "2") (pinfunction "2_2") (pintype "input"))
    )
    (net (code "20") (name "Net-(D1_R1-C)") (class "Default")
      (node (ref "D1_R1") (pin "1") (pinfunction "C_1") (pintype "input"))
      (node (ref "R1_R1") (pin "1") (pinfunction "1_1") (pintype "input"))
      (node (ref "U1_R1") (pin "7") (pinfunction "HO_7") (pintype "input"))
    )
    (net (code "21") (name "Net-(D1_R2-A)") (class "Default")
      (node (ref "D1_R2") (pin "2") (pinfunction "A_2") (pintype "input"))
      (node (ref "Q1_R2") (pin "1") (pinfunction "G_1") (pintype "input"))
      (node (ref "R1_R2") (pin "2") (pinfunction "2_2") (pintype "input"))
    )
    (net (code "22") (name "Net-(D1_R2-C)") (class "Default")
      (node (ref "D1_R2") (pin "1") (pinfunction "C_1") (pintype "input"))
      (node (ref "R1_R2") (pin "1") (pinfunction "1_1") (pintype "input"))
      (node (ref "U1_R2") (pin "7") (pinfunction "HO_7") (pintype "input"))
    )
    (net (code "23") (name "Net-(D2_L1-A)") (class "Default")
      (node (ref "D2_L1") (pin "2") (pinfunction "A_2") (pintype "input"))
      (node (ref "Q2_L1") (pin "1") (pinfunction "G_1") (pintype "input"))
      (node (ref "R2_L1") (pin "2") (pinfunction "2_2") (pintype "input"))
    )
    (net (code "24") (name "Net-(D2_L1-C)") (class "Default")
      (node (ref "D2_L1") (pin "1") (pinfunction "C_1") (pintype "input"))
      (node (ref "R2_L1") (pin "1") (pinfunction "1_1") (pintype "input"))
      (node (ref "U1_L1") (pin "5") (pinfunction "LO_5") (pintype "input"))
    )
    (net (code "25") (name "Net-(D2_L2-A)") (class "Default")
      (node (ref "D2_L2") (pin "2") (pinfunction "A_2") (pintype "input"))
      (node (ref "Q2_L2") (pin "1") (pinfunction "G_1") (pintype "input"))
      (node (ref "R2_L2") (pin "2") (pinfunction "2_2") (pintype "input"))
    )
    (net (code "26") (name "Net-(D2_L2-C)") (class "Default")
      (node (ref "D2_L2") (pin "1") (pinfunction "C_1") (pintype "input"))
      (node (ref "R2_L2") (pin "1") (pinfunction "1_1") (pintype "input"))
      (node (ref "U1_L2") (pin "5") (pinfunction "LO_5") (pintype "input"))
    )
    (net (code "27") (name "Net-(D2_R1-A)") (class "Default")
      (node (ref "D2_R1") (pin "2") (pinfunction "A_2") (pintype "input"))
      (node (ref "Q2_R1") (pin "1") (pinfunction "G_1") (pintype "input"))
      (node (ref "R2_R1") (pin "2") (pinfunction "2_2") (pintype "input"))
    )
    (net (code "28") (name "Net-(D2_R1-C)") (class "Default")
      (node (ref "D2_R1") (pin "1") (pinfunction "C_1") (pintype "input"))
      (node (ref "R2_R1") (pin "1") (pinfunction "1_1") (pintype "input"))
      (node (ref "U1_R1") (pin "5") (pinfunction "LO_5") (pintype "input"))
    )
    (net (code "29") (name "Net-(D2_R2-A)") (class "Default")
      (node (ref "D2_R2") (pin "2") (pinfunction "A_2") (pintype "input"))
      (node (ref "Q2_R2") (pin "1") (pinfunction "G_1") (pintype "input"))
      (node (ref "R2_R2") (pin "2") (pinfunction "2_2") (pintype "input"))
    )
    (net (code "30") (name "Net-(D2_R2-C)") (class "Default")
      (node (ref "D2_R2") (pin "1") (pinfunction "C_1") (pintype "input"))
      (node (ref "R2_R2") (pin "1") (pinfunction "1_1") (pintype "input"))
      (node (ref "U1_R2") (pin "5") (pinfunction "LO_5") (pintype "input"))
    )
    (net (code "31") (name "Net-(D5_L1-K)") (class "Default")
      (node (ref "C2_L1") (pin "1") (pinfunction "1_1") (pintype "input"))
      (node (ref "D5_L1") (pin "1") (pinfunction "K_1") (pintype "input"))
      (node (ref "U1_L1") (pin "8") (pinfunction "VB_8") (pintype "input"))
    )
    (net (code "32") (name "Net-(D5_L2-K)") (class "Default")
      (node (ref "C2_L2") (pin "1") (pinfunction "1_1") (pintype "input"))
      (node (ref "D5_L2") (pin "1") (pinfunction "K_1") (pintype "input"))
      (node (ref "U1_L2") (pin "8") (pinfunction "VB_8") (pintype "input"))
    )
    (net (code "33") (name "Net-(D5_R1-K)") (class "Default")
      (node (ref "C2_R1") (pin "1") (pinfunction "1_1") (pintype "input"))
      (node (ref "D5_R1") (pin "1") (pinfunction "K_1") (pintype "input"))
      (node (ref "U1_R1") (pin "8") (pinfunction "VB_8") (pintype "input"))
    )
    (net (code "34") (name "Net-(D5_R2-K)") (class "Default")
      (node (ref "C2_R2") (pin "1") (pinfunction "1_1") (pintype "input"))
      (node (ref "D5_R2") (pin "1") (pinfunction "K_1") (pintype "input"))
      (node (ref "U1_R2") (pin "8") (pinfunction "VB_8") (pintype "input"))
    )
    (net (code "35") (name "Net-(LED1-A)") (class "Default")
      (node (ref "LED1") (pin "2") (pinfunction "A_2") (pintype "input"))
      (node (ref "R2") (pin "2") (pinfunction "2_2") (pintype "input"))
    )
    (net (code "36") (name "Net-(LED2-A)") (class "Default")
      (node (ref "LED2") (pin "2") (pinfunction "A_2") (pintype "input"))
      (node (ref "R3") (pin "1") (pinfunction "1_1") (pintype "input"))
    )
    (net (code "37") (name "Net-(LED3-A)") (class "Default")
      (node (ref "LED3") (pin "2") (pinfunction "A_2") (pintype "input"))
      (node (ref "R11") (pin "2") (pinfunction "2_2") (pintype "input"))
    )
    (net (code "38") (name "Net-(R4-Pad2)") (class "Default")
      (node (ref "R4") (pin "2") (pinfunction "2_2") (pintype "input"))
      (node (ref "R6") (pin "2") (pinfunction "2_2") (pintype "input"))
    )
    (net (code "39") (name "Net-(U3-FB)") (class "Default")
      (node (ref "R5") (pin "1") (pinfunction "1_1") (pintype "input"))
      (node (ref "R6") (pin "1") (pinfunction "1_1") (pintype "input"))
      (node (ref "U3") (pin "3") (pinfunction "FB_3") (pintype "input"))
    )
    (net (code "40") (name "Net-(U4-A1)") (class "Default")
      (node (ref "H1") (pin "5") (pinfunction "5_5") (pintype "input"))
      (node (ref "U4") (pin "2") (pinfunction "A1_2") (pintype "input"))
    )
    (net (code "41") (name "Net-(U4-A2)") (class "Default")
      (node (ref "H1") (pin "4") (pinfunction "4_4") (pintype "input"))
      (node (ref "U4") (pin "3") (pinfunction "A2_3") (pintype "input"))
    )
    (net (code "42") (name "Net-(U4-A3)") (class "Default")
      (node (ref "H1") (pin "3") (pinfunction "3_3") (pintype "input"))
      (node (ref "U4") (pin "4") (pinfunction "A3_4") (pintype "input"))
    )
    (net (code "43") (name "Net-(U4-A4)") (class "Default")
      (node (ref "H1") (pin "2") (pinfunction "2_2") (pintype "input"))
      (node (ref "U4") (pin "5") (pinfunction "A4_5") (pintype "input"))
    )
    (net (code "44") (name "PGND") (class "Default")
      (node (ref "C13") (pin "2") (pinfunction "2_2") (pintype "input"))
      (node (ref "CN1") (pin "1") (pinfunction "-_1") (pintype "input"))
      (node (ref "D4_L1") (pin "2") (pinfunction "A_2") (pintype "input"))
      (node (ref "D4_L2") (pin "2") (pinfunction "A_2") (pintype "input"))
      (node (ref "D4_R1") (pin "2") (pinfunction "A_2") (pintype "input"))
      (node (ref "D4_R2") (pin "2") (pinfunction "A_2") (pintype "input"))
      (node (ref "Q2_L1") (pin "3") (pinfunction "S_3") (pintype "input"))
      (node (ref "Q2_L2") (pin "3") (pinfunction "S_3") (pintype "input"))
      (node (ref "Q2_R1") (pin "3") (pinfunction "S_3") (pintype "input"))
      (node (ref "Q2_R2") (pin "3") (pinfunction "S_3") (pintype "input"))
      (node (ref "R12") (pin "1") (pinfunction "1_1") (pintype "input"))
    )
    (net (code "45") (name "VBAT") (class "Default")
      (node (ref "C1") (pin "2") (pinfunction "2_2") (pintype "input"))
      (node (ref "C10") (pin "2") (pinfunction "2_2") (pintype "input"))
      (node (ref "C2") (pin "2") (pinfunction "2_2") (pintype "input"))
      (node (ref "C9") (pin "2") (pinfunction "2_2") (pintype "input"))
      (node (ref "D3_L1") (pin "1") (pinfunction "C_1") (pintype "input"))
      (node (ref "D3_L2") (pin "1") (pinfunction "C_1") (pintype "input"))
      (node (ref "D3_R1") (pin "1") (pinfunction "C_1") (pintype "input"))
      (node (ref "D3_R2") (pin "1") (pinfunction "C_1") (pintype "input"))
      (node (ref "L1") (pin "2") (pinfunction "2_2") (pintype "input"))
      (node (ref "Q1_L1") (pin "2") (pinfunction "D_2") (pintype "input"))
      (node (ref "Q1_L2") (pin "2") (pinfunction "D_2") (pintype "input"))
      (node (ref "Q1_R1") (pin "2") (pinfunction "D_2") (pintype "input"))
      (node (ref "Q1_R2") (pin "2") (pinfunction "D_2") (pintype "input"))
      (node (ref "U2") (pin "3") (pinfunction "VIN_3") (pintype "input"))
      (node (ref "U3") (pin "4") (pinfunction "EN_4") (pintype "input"))
      (node (ref "U3") (pin "5") (pinfunction "VIN_5") (pintype "input"))
      (node (ref "U5") (pin "2") (pinfunction "2_2") (pintype "input"))
    )
    (net (code "46") (name "unconnected-(U1-VOUT(TAB)-Pad2)") (class "Default")
      (node (ref "U1") (pin "2") (pinfunction "VOUT(TAB)_2") (pintype "input+no_connect"))
    )
    (net (code "47") (name "unconnected-(U2-VOUT(TAB)-Pad2)") (class "Default")
      (node (ref "U2") (pin "2") (pinfunction "VOUT(TAB)_2") (pintype "input+no_connect"))
    )
    (net (code "48") (name "unconnected-(U3-NC-Pad6)") (class "Default")
      (node (ref "U3") (pin "6") (pinfunction "NC_6") (pintype "input+no_connect"))
    )
    (net (code "49") (name "unconnected-(U5-Pad3)") (class "Default")
      (node (ref "U5") (pin "3") (pinfunction "3_3") (pintype "input+no_connect"))
    )
  )
)
